# LTC6268_circuit.net
KiCad netlist of a schematic drawn in Altium Designer
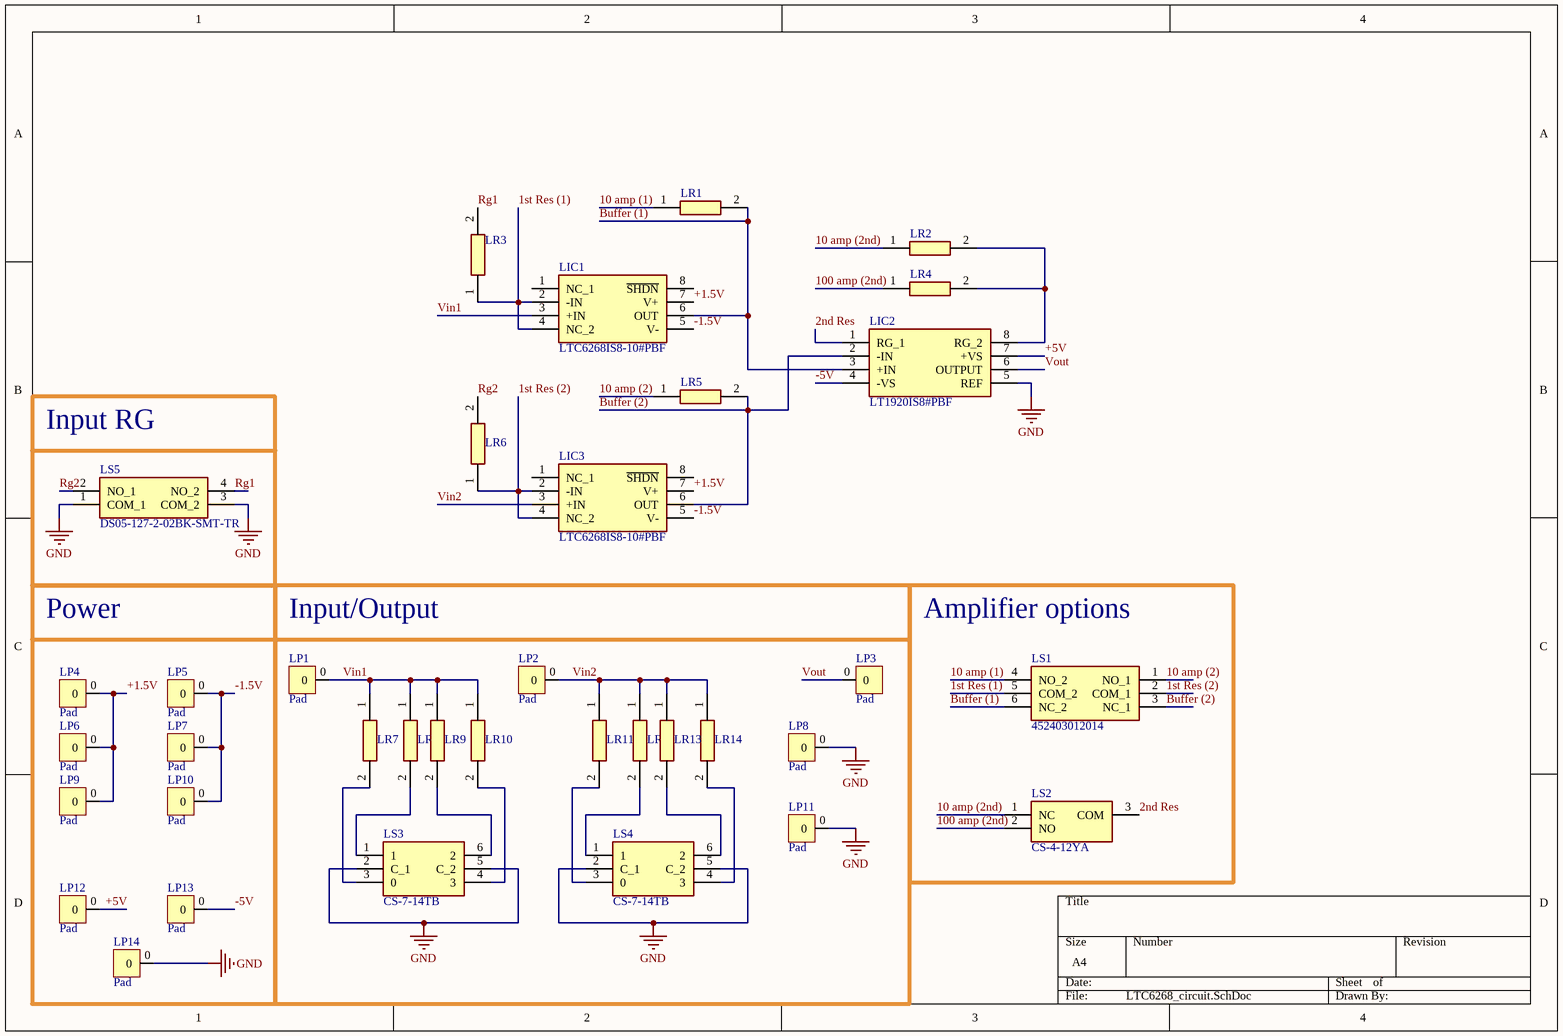
[diagram p0: LTC6268_circuit.SchDoc]

(export (version "E")
  (design (tool "Eeschema 10.0.6"))
  (components
    (comp (ref "LIC1")
      (value "LTC6268IS8-10#PBF")
      (footprint "SamacSys:SOIC127P599X175-8N")
      (description "Integrated Circuit")
      (fields (field (name "MOUSER PART NUMBER") "584-LTC6268IS8-10PBF"))
      (libsource (lib "SamacSys") (part "LTC6268IS8-10#PBF"))
    )
    (comp (ref "LIC2")
      (value "LT1920IS8#PBF")
      (footprint "SamacSys:SOIC127P599X175-8N")
      (description "Integrated Circuit")
      (fields (field (name "MOUSER PART NUMBER") "584-LT1920IS8#PBF"))
      (libsource (lib "SamacSys") (part "LT1920IS8#PBF"))
    )
    (comp (ref "LIC3")
      (value "LTC6268IS8-10#PBF")
      (footprint "SamacSys:SOIC127P599X175-8N")
      (description "Integrated Circuit")
      (fields (field (name "MOUSER PART NUMBER") "584-LTC6268IS8-10PBF"))
      (libsource (lib "SamacSys") (part "LTC6268IS8-10#PBF"))
    )
    (comp (ref "LP1") (value "Pad") (footprint "Pad") (libsource (lib "SamacSys") (part "Pad")))
    (comp (ref "LP2") (value "Pad") (footprint "Pad") (libsource (lib "SamacSys") (part "Pad")))
    (comp (ref "LP3") (value "Pad") (footprint "Pad") (libsource (lib "") (part "Pad_1")))
    (comp (ref "LP4") (value "Pad") (footprint "Pad") (libsource (lib "SamacSys") (part "Pad")))
    (comp (ref "LP5") (value "Pad") (footprint "Pad") (libsource (lib "SamacSys") (part "Pad")))
    (comp (ref "LP6") (value "Pad") (footprint "Pad") (libsource (lib "SamacSys") (part "Pad")))
    (comp (ref "LP7") (value "Pad") (footprint "Pad") (libsource (lib "SamacSys") (part "Pad")))
    (comp (ref "LP8") (value "Pad") (footprint "Pad") (libsource (lib "SamacSys") (part "Pad")))
    (comp (ref "LP9") (value "Pad") (footprint "Pad") (libsource (lib "SamacSys") (part "Pad")))
    (comp (ref "LP10") (value "Pad") (footprint "Pad") (libsource (lib "SamacSys") (part "Pad")))
    (comp (ref "LP11") (value "Pad") (footprint "Pad") (libsource (lib "SamacSys") (part "Pad")))
    (comp (ref "LP12") (value "Pad") (footprint "Pad") (libsource (lib "SamacSys") (part "Pad")))
    (comp (ref "LP13") (value "Pad") (footprint "Pad") (libsource (lib "SamacSys") (part "Pad")))
    (comp (ref "LP14") (value "Pad") (footprint "Pad") (libsource (lib "SamacSys") (part "Pad")))
    (comp (ref "LR1")
      (value "CRG0805F270R")
      (footprint "SamacSys:RESC2012X65N")
      (description "Resistor 270")
      (fields (field (name "MOUSER PART NUMBER") "279-CRG0805F270R"))
      (libsource (lib "SamacSys") (part "CRG0805F270R"))
    )
    (comp (ref "LR2")
      (value "CRG0805F4K7")
      (footprint "SamacSys:RESC2012X65N")
      (description "Resistor 4.7k")
      (fields (field (name "MOUSER PART NUMBER") "279-CRG0805F4K7"))
      (libsource (lib "SamacSys") (part "CRG0805F4K7"))
    )
    (comp (ref "LR3")
      (value "ERJ-HP6F20R0V")
      (footprint "SamacSys:ERJHP6D1000V")
      (description "Resistor 20")
      (libsource (lib "SamacSys") (part "ERJ-HP6F20R0V"))
    )
    (comp (ref "LR4")
      (value "CRG0805F330R")
      (footprint "SamacSys:RESC2012X65N")
      (description "Resistor 330")
      (fields (field (name "MOUSER PART NUMBER") "279-CRG0805F330R"))
      (libsource (lib "SamacSys") (part "CRG0805F330R"))
    )
    (comp (ref "LR5")
      (value "CRG0805F270R")
      (footprint "SamacSys:RESC2012X65N")
      (description "Resistor 270")
      (fields (field (name "MOUSER PART NUMBER") "279-CRG0805F270R"))
      (libsource (lib "SamacSys") (part "CRG0805F270R"))
    )
    (comp (ref "LR6")
      (value "ERJ-HP6F20R0V")
      (footprint "SamacSys:ERJHP6D1000V")
      (description "Resistor 20")
      (libsource (lib "SamacSys") (part "ERJ-HP6F20R0V"))
    )
    (comp (ref "LR7")
      (value "RH73X2A10GNTN")
      (footprint "SamacSys:RESC2013X50N")
      (description "Resistor 10G")
      (fields (field (name "MOUSER PART NUMBER") "279-RH73X2A10GNTN"))
      (libsource (lib "SamacSys") (part "RH73X2A10GNTN"))
    )
    (comp (ref "LR8")
      (value "RH73X2A50GNTN")
      (footprint "SamacSys:RESC2013X50N")
      (description "Resistor 50G")
      (fields (field (name "MOUSER PART NUMBER") "279-RH73X2A50GNTN"))
      (libsource (lib "SamacSys") (part "RH73X2A50GNTN"))
    )
    (comp (ref "LR9")
      (value "RH73H2A100MKTN")
      (footprint "SamacSys:RESC2013X50N")
      (description "Resistor 100M")
      (fields (field (name "MOUSER PART NUMBER") "279-RH73H2A100MKTN"))
      (libsource (lib "SamacSys") (part "RH73H2A100MKTN"))
    )
    (comp (ref "LR10")
      (value "RH73W2A1GNTN")
      (footprint "SamacSys:RESC2013X50N")
      (description "Resistor 1G")
      (fields (field (name "MOUSER PART NUMBER") "279-RH73W2A1GNTN"))
      (libsource (lib "SamacSys") (part "RH73W2A1GNTN"))
    )
    (comp (ref "LR11")
      (value "RH73X2A50GNTN")
      (footprint "SamacSys:RESC2013X50N")
      (description "Resistor 50G")
      (fields (field (name "MOUSER PART NUMBER") "279-RH73X2A50GNTN"))
      (libsource (lib "SamacSys") (part "RH73X2A50GNTN"))
    )
    (comp (ref "LR12")
      (value "RH73X2A10GNTN")
      (footprint "SamacSys:RESC2013X50N")
      (description "Resistor 10G")
      (fields (field (name "MOUSER PART NUMBER") "279-RH73X2A10GNTN"))
      (libsource (lib "SamacSys") (part "RH73X2A10GNTN"))
    )
    (comp (ref "LR13")
      (value "RH73W2A1GNTN")
      (footprint "SamacSys:RESC2013X50N")
      (description "Resistor 1G")
      (fields (field (name "MOUSER PART NUMBER") "279-RH73W2A1GNTN"))
      (libsource (lib "SamacSys") (part "RH73W2A1GNTN"))
    )
    (comp (ref "LR14")
      (value "RH73H2A100MKTN")
      (footprint "SamacSys:RESC2013X50N")
      (description "Resistor 100M")
      (fields (field (name "MOUSER PART NUMBER") "279-RH73H2A100MKTN"))
      (libsource (lib "SamacSys") (part "RH73H2A100MKTN"))
    )
    (comp (ref "LS1")
      (value "452403012014")
      (footprint "SamacSys:452403012014")
      (description "Switch")
      (fields (field (name "MOUSER PART NUMBER") "710-452403012014"))
      (libsource (lib "SamacSys") (part "452403012014"))
    )
    (comp (ref "LS2")
      (value "CS-4-12YA")
      (footprint "SamacSys:CS412YA")
      (description "Switch")
      (libsource (lib "SamacSys") (part "CS-4-12YA"))
    )
    (comp (ref "LS3")
      (value "CS-7-14TB")
      (footprint "SamacSys:SOP254P1000X405-6N")
      (description "Switch")
      (libsource (lib "SamacSys") (part "CS-7-14TB"))
    )
    (comp (ref "LS4")
      (value "CS-7-14TB")
      (footprint "SamacSys:SOP254P1000X405-6N")
      (description "Switch")
      (libsource (lib "SamacSys") (part "CS-7-14TB"))
    )
    (comp (ref "LS5")
      (value "DS05-127-2-02BK-SMT-TR")
      (footprint "SamacSys:DS05127202BKSMTTR")
      (description "Switch")
      (fields (field (name "MOUSER PART NUMBER") "490-DS05127202BK-STR"))
      (libsource (lib "SamacSys") (part "DS05-127-2-02BK-SMT-TR"))
    )
  )
  (nets
    (net (code "1") (name "/+1.5V") (class "Default")
      (node (ref "LIC1") (pin "7") (pinfunction "V+_7") (pintype "passive"))
      (node (ref "LIC3") (pin "7") (pinfunction "V+_7") (pintype "passive"))
      (node (ref "LP4") (pin "0") (pinfunction "0_0") (pintype "passive"))
      (node (ref "LP6") (pin "0") (pinfunction "0_0") (pintype "passive"))
      (node (ref "LP9") (pin "0") (pinfunction "0_0") (pintype "passive"))
    )
    (net (code "2") (name "/+5V") (class "Default")
      (node (ref "LIC2") (pin "7") (pinfunction "+VS_7") (pintype "passive"))
      (node (ref "LP12") (pin "0") (pinfunction "0_0") (pintype "passive"))
    )
    (net (code "3") (name "/-1.5V") (class "Default")
      (node (ref "LIC1") (pin "5") (pinfunction "V-_5") (pintype "passive"))
      (node (ref "LIC3") (pin "5") (pinfunction "V-_5") (pintype "passive"))
      (node (ref "LP10") (pin "0") (pinfunction "0_0") (pintype "passive"))
      (node (ref "LP5") (pin "0") (pinfunction "0_0") (pintype "passive"))
      (node (ref "LP7") (pin "0") (pinfunction "0_0") (pintype "passive"))
    )
    (net (code "4") (name "/-5V") (class "Default")
      (node (ref "LIC2") (pin "4") (pinfunction "-VS_4") (pintype "passive"))
      (node (ref "LP13") (pin "0") (pinfunction "0_0") (pintype "passive"))
    )
    (net (code "5") (name "/1st Res (1)") (class "Default")
      (node (ref "LIC1") (pin "2") (pinfunction "-IN_2") (pintype "passive"))
      (node (ref "LIC1") (pin "4") (pinfunction "NC_2_4") (pintype "passive"))
      (node (ref "LR3") (pin "1") (pinfunction "1_1") (pintype "passive"))
      (node (ref "LS1") (pin "5") (pinfunction "COM_2_5") (pintype "passive"))
    )
    (net (code "6") (name "/1st Res (2)") (class "Default")
      (node (ref "LIC3") (pin "2") (pinfunction "-IN_2") (pintype "passive"))
      (node (ref "LIC3") (pin "4") (pinfunction "NC_2_4") (pintype "passive"))
      (node (ref "LR6") (pin "1") (pinfunction "1_1") (pintype "passive"))
      (node (ref "LS1") (pin "2") (pinfunction "COM_1_2") (pintype "passive"))
    )
    (net (code "7") (name "/2nd Res") (class "Default")
      (node (ref "LIC2") (pin "1") (pinfunction "RG_1_1") (pintype "passive"))
      (node (ref "LS2") (pin "3") (pinfunction "COM_3") (pintype "passive"))
    )
    (net (code "8") (name "/10 amp (1)") (class "Default")
      (node (ref "LR1") (pin "1") (pinfunction "1_1") (pintype "passive"))
      (node (ref "LS1") (pin "4") (pinfunction "NO_2_4") (pintype "passive"))
    )
    (net (code "9") (name "/10 amp (2)") (class "Default")
      (node (ref "LR5") (pin "1") (pinfunction "1_1") (pintype "passive"))
      (node (ref "LS1") (pin "1") (pinfunction "NO_1_1") (pintype "passive"))
    )
    (net (code "10") (name "/10 amp (2nd)") (class "Default")
      (node (ref "LR2") (pin "1") (pinfunction "1_1") (pintype "passive"))
      (node (ref "LS2") (pin "1") (pinfunction "NC_1") (pintype "passive"))
    )
    (net (code "11") (name "/100 amp (2nd)") (class "Default")
      (node (ref "LR4") (pin "1") (pinfunction "1_1") (pintype "passive"))
      (node (ref "LS2") (pin "2") (pinfunction "NO_2") (pintype "passive"))
    )
    (net (code "12") (name "/Buffer (1)") (class "Default")
      (node (ref "LIC1") (pin "6") (pinfunction "OUT_6") (pintype "passive"))
      (node (ref "LIC2") (pin "3") (pinfunction "+IN_3") (pintype "passive"))
      (node (ref "LR1") (pin "2") (pinfunction "2_2") (pintype "passive"))
      (node (ref "LS1") (pin "6") (pinfunction "NC_2_6") (pintype "passive"))
    )
    (net (code "13") (name "/Buffer (2)") (class "Default")
      (node (ref "LIC2") (pin "2") (pinfunction "-IN_2") (pintype "passive"))
      (node (ref "LIC3") (pin "6") (pinfunction "OUT_6") (pintype "passive"))
      (node (ref "LR5") (pin "2") (pinfunction "2_2") (pintype "passive"))
      (node (ref "LS1") (pin "3") (pinfunction "NC_1_3") (pintype "passive"))
    )
    (net (code "14") (name "/Rg1") (class "Default")
      (node (ref "LR3") (pin "2") (pinfunction "2_2") (pintype "passive"))
      (node (ref "LS5") (pin "4") (pinfunction "NO_2_4") (pintype "passive"))
    )
    (net (code "15") (name "/Rg2") (class "Default")
      (node (ref "LR6") (pin "2") (pinfunction "2_2") (pintype "passive"))
      (node (ref "LS5") (pin "2") (pinfunction "NO_1_2") (pintype "passive"))
    )
    (net (code "16") (name "/Vin1") (class "Default")
      (node (ref "LIC1") (pin "3") (pinfunction "+IN_3") (pintype "passive"))
      (node (ref "LP1") (pin "0") (pinfunction "0_0") (pintype "passive"))
      (node (ref "LR10") (pin "1") (pinfunction "1_1") (pintype "passive"))
      (node (ref "LR7") (pin "1") (pinfunction "1_1") (pintype "passive"))
      (node (ref "LR8") (pin "1") (pinfunction "1_1") (pintype "passive"))
      (node (ref "LR9") (pin "1") (pinfunction "1_1") (pintype "passive"))
    )
    (net (code "17") (name "/Vin2") (class "Default")
      (node (ref "LIC3") (pin "3") (pinfunction "+IN_3") (pintype "passive"))
      (node (ref "LP2") (pin "0") (pinfunction "0_0") (pintype "passive"))
      (node (ref "LR11") (pin "1") (pinfunction "1_1") (pintype "passive"))
      (node (ref "LR12") (pin "1") (pinfunction "1_1") (pintype "passive"))
      (node (ref "LR13") (pin "1") (pinfunction "1_1") (pintype "passive"))
      (node (ref "LR14") (pin "1") (pinfunction "1_1") (pintype "passive"))
    )
    (net (code "18") (name "/Vout") (class "Default")
      (node (ref "LIC2") (pin "6") (pinfunction "OUTPUT_6") (pintype "passive"))
      (node (ref "LP3") (pin "0") (pinfunction "0_0") (pintype "passive"))
    )
    (net (code "19") (name "GND") (class "Default")
      (node (ref "LIC2") (pin "5") (pinfunction "REF_5") (pintype "passive"))
      (node (ref "LP11") (pin "0") (pinfunction "0_0") (pintype "passive"))
      (node (ref "LP14") (pin "0") (pinfunction "0_0") (pintype "passive"))
      (node (ref "LP8") (pin "0") (pinfunction "0_0") (pintype "passive"))
      (node (ref "LS3") (pin "2") (pinfunction "C_1_2") (pintype "passive"))
      (node (ref "LS3") (pin "5") (pinfunction "C_2_5") (pintype "passive"))
      (node (ref "LS4") (pin "2") (pinfunction "C_1_2") (pintype "passive"))
      (node (ref "LS4") (pin "5") (pinfunction "C_2_5") (pintype "passive"))
      (node (ref "LS5") (pin "1") (pinfunction "COM_1_1") (pintype "passive"))
      (node (ref "LS5") (pin "3") (pinfunction "COM_2_3") (pintype "passive"))
    )
    (net (code "20") (name "Net-(LIC2-RG_2)") (class "Default")
      (node (ref "LIC2") (pin "8") (pinfunction "RG_2_8") (pintype "passive"))
      (node (ref "LR2") (pin "2") (pinfunction "2_2") (pintype "passive"))
      (node (ref "LR4") (pin "2") (pinfunction "2_2") (pintype "passive"))
    )
    (net (code "21") (name "Net-(LR8-Pad2)") (class "Default")
      (node (ref "LR8") (pin "2") (pinfunction "2_2") (pintype "passive"))
      (node (ref "LS3") (pin "1") (pinfunction "1_1") (pintype "passive"))
    )
    (net (code "22") (name "Net-(LR12-Pad2)") (class "Default")
      (node (ref "LR12") (pin "2") (pinfunction "2_2") (pintype "passive"))
      (node (ref "LS4") (pin "1") (pinfunction "1_1") (pintype "passive"))
    )
    (net (code "23") (name "Net-(LS3-0)") (class "Default")
      (node (ref "LR7") (pin "2") (pinfunction "2_2") (pintype "passive"))
      (node (ref "LS3") (pin "3") (pinfunction "0_3") (pintype "passive"))
    )
    (net (code "24") (name "Net-(LS3-2)") (class "Default")
      (node (ref "LR9") (pin "2") (pinfunction "2_2") (pintype "passive"))
      (node (ref "LS3") (pin "6") (pinfunction "2_6") (pintype "passive"))
    )
    (net (code "25") (name "Net-(LS3-3)") (class "Default")
      (node (ref "LR10") (pin "2") (pinfunction "2_2") (pintype "passive"))
      (node (ref "LS3") (pin "4") (pinfunction "3_4") (pintype "passive"))
    )
    (net (code "26") (name "Net-(LS4-0)") (class "Default")
      (node (ref "LR11") (pin "2") (pinfunction "2_2") (pintype "passive"))
      (node (ref "LS4") (pin "3") (pinfunction "0_3") (pintype "passive"))
    )
    (net (code "27") (name "Net-(LS4-2)") (class "Default")
      (node (ref "LR13") (pin "2") (pinfunction "2_2") (pintype "passive"))
      (node (ref "LS4") (pin "6") (pinfunction "2_6") (pintype "passive"))
    )
    (net (code "28") (name "Net-(LS4-3)") (class "Default")
      (node (ref "LR14") (pin "2") (pinfunction "2_2") (pintype "passive"))
      (node (ref "LS4") (pin "4") (pinfunction "3_4") (pintype "passive"))
    )
    (net (code "29") (name "unconnected-(LIC1-NC_1-Pad1)") (class "Default")
      (node (ref "LIC1") (pin "1") (pinfunction "NC_1_1") (pintype "passive"))
    )
    (net (code "30") (name "unconnected-(LIC1-~{SHDN}-Pad8)") (class "Default")
      (node (ref "LIC1") (pin "8") (pinfunction "~{SHDN}_8") (pintype "passive"))
    )
    (net (code "31") (name "unconnected-(LIC3-NC_1-Pad1)") (class "Default")
      (node (ref "LIC3") (pin "1") (pinfunction "NC_1_1") (pintype "passive"))
    )
    (net (code "32") (name "unconnected-(LIC3-~{SHDN}-Pad8)") (class "Default")
      (node (ref "LIC3") (pin "8") (pinfunction "~{SHDN}_8") (pintype "passive"))
    )
  )
)
